# 12V_Buck_For_Auton_LED.net
KiCad netlist of a schematic drawn in Altium Designer
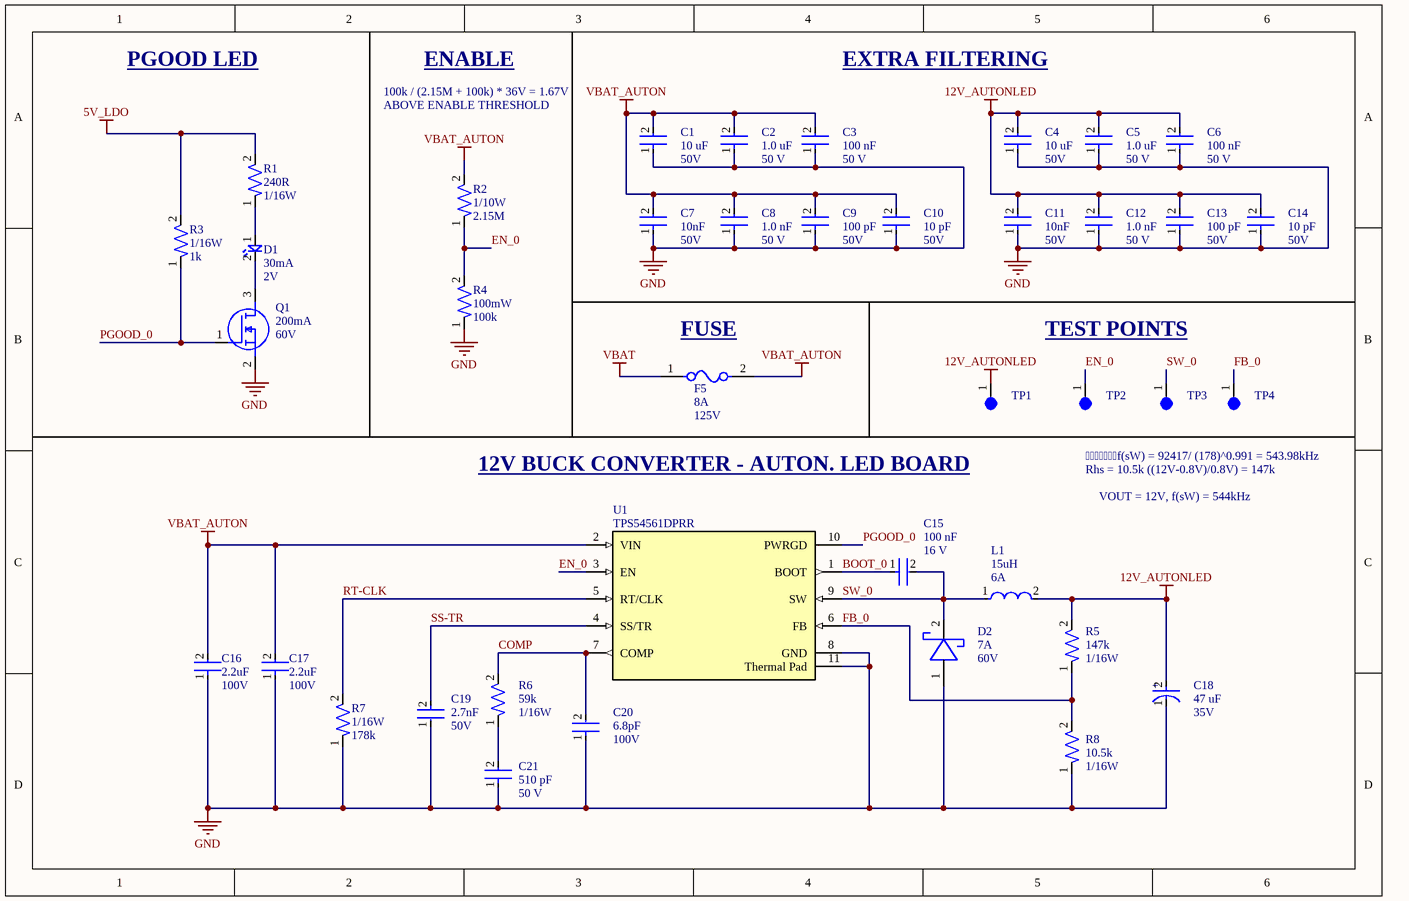
[diagram p0: 12V_Buck_For_Auton_LED.SchDoc]

(export (version "E")
  (design (tool "Eeschema 10.0.6"))
  (components
    (comp (ref "C1")
      (value "CL32B106KBJNNNE")
      (footprint "CAP-1210")
      (description "CAP CER 10UF 50V X7R 1210")
      (fields (field (name "VOLTAGE") "50V") (field (name "CAPACITANCE") "10 uF"))
      (libsource (lib "JLC_25") (part "CAP-10U-0002"))
    )
    (comp (ref "C2")
      (value "CC0805KKX7R9BB105")
      (footprint "CAP-0805")
      (description "CAP CER 1UF 50V X7R 0805")
      (fields (field (name "VOLTAGE") "50 V") (field (name "CAPACITANCE") "1.0 uF"))
      (libsource (lib "JLC_25") (part "CAP-1U-0001"))
    )
    (comp (ref "C3")
      (value "CC0805KRX7R9BB104")
      (footprint "CAP-0805")
      (description "CAP CER 0.1UF 50V X7R 0805")
      (fields (field (name "VOLTAGE RATING") "50 V") (field (name "CAPACITANCE") "100 nF"))
      (libsource (lib "JLC_25") (part "CAP-0.1U-0002"))
    )
    (comp (ref "C4")
      (value "CL32B106KBJNNNE")
      (footprint "CAP-1210")
      (description "CAP CER 10UF 50V X7R 1210")
      (fields (field (name "VOLTAGE") "50V") (field (name "CAPACITANCE") "10 uF"))
      (libsource (lib "JLC_25") (part "CAP-10U-0002"))
    )
    (comp (ref "C5")
      (value "CC0805KKX7R9BB105")
      (footprint "CAP-0805")
      (description "CAP CER 1UF 50V X7R 0805")
      (fields (field (name "VOLTAGE") "50 V") (field (name "CAPACITANCE") "1.0 uF"))
      (libsource (lib "JLC_25") (part "CAP-1U-0001"))
    )
    (comp (ref "C6")
      (value "CC0805KRX7R9BB104")
      (footprint "CAP-0805")
      (description "CAP CER 0.1UF 50V X7R 0805")
      (fields (field (name "VOLTAGE RATING") "50 V") (field (name "CAPACITANCE") "100 nF"))
      (libsource (lib "JLC_25") (part "CAP-0.1U-0002"))
    )
    (comp (ref "C7")
      (value "GRM2195C1H103JA01D")
      (footprint "CAP-0805")
      (description "CAP CER 10000PF 50V C0G/NP0 0805")
      (fields (field (name "VOLTAGE") "50V") (field (name "CAPACITANCE") "10nF"))
      (libsource (lib "JLC_25") (part "CAP-10N-0001"))
    )
    (comp (ref "C8")
      (value "CC0402KRX7R9BB102")
      (footprint "CAP-0402")
      (description "CAP CER 1000PF 50V X7R 0402")
      (fields (field (name "VOLTAGE") "50 V") (field (name "CAPACITANCE") "1.0 nF"))
      (libsource (lib "JLC_25") (part "CAP-1N-0001"))
    )
    (comp (ref "C9")
      (value "CC0402JRNPO9BN101")
      (footprint "CAP-0402")
      (description "CAP CER 100PF 50V C0G/NPO 0402")
      (fields (field (name "CAPACITANCE") "100 pF") (field (name "VOLTAGE") "50V"))
      (libsource (lib "JLC_25") (part "CAP-100P-0001"))
    )
    (comp (ref "C10")
      (value "CC0402JRNPO9BN100")
      (footprint "CAP-0402")
      (description "CAP CER 10PF 50V C0G/NPO 0402")
      (fields (field (name "CAPACITANCE") "10 pF") (field (name "VOLTAGE") "50V"))
      (libsource (lib "JLC_25") (part "CAP-10P-0001"))
    )
    (comp (ref "C11")
      (value "GRM2195C1H103JA01D")
      (footprint "CAP-0805")
      (description "CAP CER 10000PF 50V C0G/NP0 0805")
      (fields (field (name "VOLTAGE") "50V") (field (name "CAPACITANCE") "10nF"))
      (libsource (lib "JLC_25") (part "CAP-10N-0001"))
    )
    (comp (ref "C12")
      (value "CC0402KRX7R9BB102")
      (footprint "CAP-0402")
      (description "CAP CER 1000PF 50V X7R 0402")
      (fields (field (name "VOLTAGE") "50 V") (field (name "CAPACITANCE") "1.0 nF"))
      (libsource (lib "JLC_25") (part "CAP-1N-0001"))
    )
    (comp (ref "C13")
      (value "CC0402JRNPO9BN101")
      (footprint "CAP-0402")
      (description "CAP CER 100PF 50V C0G/NPO 0402")
      (fields (field (name "CAPACITANCE") "100 pF") (field (name "VOLTAGE") "50V"))
      (libsource (lib "JLC_25") (part "CAP-100P-0001"))
    )
    (comp (ref "C14")
      (value "CC0402JRNPO9BN100")
      (footprint "CAP-0402")
      (description "CAP CER 10PF 50V C0G/NPO 0402")
      (fields (field (name "CAPACITANCE") "10 pF") (field (name "VOLTAGE") "50V"))
      (libsource (lib "JLC_25") (part "CAP-10P-0001"))
    )
    (comp (ref "C15")
      (value "CC0402KRX7R7BB104")
      (footprint "CAP-0402")
      (description "CAP CER 0.1UF 16V X7R 0402")
      (fields (field (name "VOLTAGE RATING") "16 V") (field (name "CAPACITANCE") "100 nF"))
      (libsource (lib "JLC_25") (part "CAP-0.1U-0001"))
    )
    (comp (ref "C16")
      (value "CC1206KKX7R0BB225")
      (footprint "CAP-1206")
      (description "CAP CER 2.2UF 100V X7R 1206")
      (fields (field (name "CAPACITANCE") "2.2uF") (field (name "VOLTAGE") "100V"))
      (libsource (lib "JLC_25") (part "CAP-2.2U-0001"))
    )
    (comp (ref "C17")
      (value "CC1206KKX7R0BB225")
      (footprint "CAP-1206")
      (description "CAP CER 2.2UF 100V X7R 1206")
      (fields (field (name "CAPACITANCE") "2.2uF") (field (name "VOLTAGE") "100V"))
      (libsource (lib "JLC_25") (part "CAP-2.2U-0001"))
    )
    (comp (ref "C18")
      (value "EEH-ZC1V470P")
      (footprint "CAP_EEHZC1V470P")
      (description "47 µF 35 V Aluminum - Polymer Capacitors Radial, Can - SMD 60mOhm 4000 Hrs @ 125°C")
      (fields (field (name "VOLTAGE") "35V") (field (name "CAPACITANCE") "47 uF"))
      (libsource (lib "JLC_25") (part "CAP-47U-0003"))
    )
    (comp (ref "C19")
      (value "GRM2165C1H272JA01D")
      (footprint "CAP-0805")
      (description "CAP CER 2700PF 50V C0G/NP0 0805")
      (fields (field (name "VOLTAGE") "50V") (field (name "CAPACITANCE") "2.7nF"))
      (libsource (lib "JLC_25") (part "CAP-2.7N-0001"))
    )
    (comp (ref "C20")
      (value "CC0603CRNPO0BN6R8")
      (footprint "CAP-0603")
      (description "CAP CER 6.8PF 100V C0G/NPO 0603")
      (fields (field (name "VOLTAGE") "100V") (field (name "CAPACITANCE") "6.8pF"))
      (libsource (lib "JLC_25") (part "CAP-6.8P-0001"))
    )
    (comp (ref "C21")
      (value "0402N511J500CT")
      (footprint "CAP-0402")
      (description "CAP CER 510PF 50V C0G/NP0 0402")
      (fields (field (name "VOLTAGE") "50 V") (field (name "CAPACITANCE") "510 pF"))
      (libsource (lib "JLC_25") (part "CAP-510P-0001"))
    )
    (comp (ref "D1")
      (value "BL-HKC36G-AV-TRB")
      (footprint "LED-0603")
      (description "LED YELLOW CLEAR 0603 SMD")
      (fields (field (name "FORWARD CURRENT") "30mA") (field (name "FORWARD VOLTAGE") "2V"))
      (libsource (lib "JLC_25") (part "LED-0001"))
    )
    (comp (ref "D2")
      (value "PDS760-13")
      (footprint "DO-POWERDI5")
      (description "DIODE SCHOTTKY 60V 7A POWERDI5")
      (fields (field (name "FORWARD CURRENT") "7A") (field (name "REVERSE VOLTAGE (DC)") "60V"))
      (libsource (lib "JLC_25") (part "DIO-SCHOTTKY-0001"))
    )
    (comp (ref "F5")
      (value "01550900M")
      (footprint "FUSE-0001")
      (description "FUSE BLOK CARTRIDGE 125V 10A SMD")
      (fields (field (name "FUSE CURRENT") "8A") (field (name "VOLTAGE RATING") "125V"))
      (libsource (lib "JLC_25") (part "FUSE-0001"))
    )
    (comp (ref "L1")
      (value "CSAD1010-150M")
      (footprint "IND-15U-0002")
      (description "SMD MOLDING POWER CHOKE")
      (fields (field (name "INDUCTANCE") "15uH") (field (name "CURRENT RATING") "6A"))
      (libsource (lib "JLC_25") (part "IND-15U-0002-NoJLC"))
    )
    (comp (ref "Q1")
      (value "T2N7002AK,LM")
      (footprint "IC-SOT23-3")
      (description "MOSFET N-CH 60V 200MA SOT23")
      (fields (field (name "CONTINUOUS CURRENT") "200mA") (field (name "VOLTAGE") "60V"))
      (libsource (lib "JLC_25") (part "NMOS-200MA-0001"))
    )
    (comp (ref "R1")
      (value "RC0402FR-07240RL")
      (footprint "RES-0402")
      (description "240R 0.063W 1% 0402 (1005 Metric)  SMD")
      (fields
        (field (name "TOLERANCE") "1%")
        (field (name "RESISTANCE") "240R")
        (field (name "POWER") "1/16W")
      )
      (libsource (lib "JLC_25") (part "RES-240-0001"))
    )
    (comp (ref "R2")
      (value "RC0603FR-072M15L")
      (footprint "RES-0603")
      (description "RES SMD 2.15M OHM 1% 1/10W 0603")
      (fields
        (field (name "TOLERANCE") "1%")
        (field (name "POWER") "1/10W")
        (field (name "RESISTANCE") "2.15M")
      )
      (libsource (lib "JLC_25") (part "RES-2.15M-0001"))
    )
    (comp (ref "R3")
      (value "RC0402FR-071KL")
      (footprint "RES-0402")
      (description "RES 1K OHM 1% 1/16W 0402")
      (fields (field (name "TOLERANCE") "1%") (field (name "POWER") "1/16W") (field (name "RESISTANCE") "1k"))
      (libsource (lib "JLC_25") (part "RES-1k-0001"))
    )
    (comp (ref "R4")
      (value "RC0603FR-07100KL")
      (footprint "RES-0603")
      (description "RES SMD 100K OHM 1% 1/10W 0603")
      (fields
        (field (name "TOLERANCE") "1%")
        (field (name "POWER") "100mW")
        (field (name "RESISTANCE") "100k")
      )
      (libsource (lib "JLC_25") (part "RES-100k-0001"))
    )
    (comp (ref "R5")
      (value "RC0402FR-07147KL")
      (footprint "RES-0402")
      (description "RES 147K OHM 1% 1/16W 0402")
      (fields
        (field (name "TOLERANCE") "1%")
        (field (name "POWER") "1/16W")
        (field (name "RESISTANCE") "147k")
      )
      (libsource (lib "JLC_25") (part "RES-147k-0001"))
    )
    (comp (ref "R6")
      (value "RC0402FR-0759KL")
      (footprint "RES-0402")
      (description "RES 59K OHM 1% 1/16W 0402")
      (fields
        (field (name "TOLERANCE") "1%")
        (field (name "POWER") "1/16W")
        (field (name "RESISTANCE") "59k")
      )
      (libsource (lib "JLC_25") (part "RES-59k-0001"))
    )
    (comp (ref "R7")
      (value "RTT021783FTH")
      (footprint "RES-0402")
      (description "62.5mW Thick Film Resistors 50V ±100ppm/℃ ±1% 178kΩ 0402 Chip Resistor - Surface Mount ROHS")
      (fields
        (field (name "TOLERANCE") "1%")
        (field (name "POWER") "1/16W")
        (field (name "RESISTANCE") "178k")
      )
      (libsource (lib "JLC_25") (part "RES-178k-0001_1"))
    )
    (comp (ref "R8")
      (value "RC0402FR-0710K5L")
      (footprint "RES-0402")
      (description "RES 10.5K OHM 1% 1/16W 0402")
      (fields
        (field (name "TOLERANCE") "1%")
        (field (name "POWER") "1/16W")
        (field (name "RESISTANCE") "10.5k")
      )
      (libsource (lib "JLC_25") (part "RES-10.5k-0001"))
    )
    (comp (ref "TP1")
      (value "5003")
      (footprint "TEST-POINT-0001")
      (description "Oranange PC Test Point, Miniature Phoisphor Bronze Silver Plating Through Hole Mounting Type")
      (libsource (lib "*") (part "TEST-POINT-0001"))
    )
    (comp (ref "TP2")
      (value "5003")
      (footprint "TEST-POINT-0001")
      (description "Oranange PC Test Point, Miniature Phoisphor Bronze Silver Plating Through Hole Mounting Type")
      (libsource (lib "*") (part "TEST-POINT-0001"))
    )
    (comp (ref "TP3")
      (value "5003")
      (footprint "TEST-POINT-0001")
      (description "Oranange PC Test Point, Miniature Phoisphor Bronze Silver Plating Through Hole Mounting Type")
      (libsource (lib "*") (part "TEST-POINT-0001"))
    )
    (comp (ref "TP4")
      (value "5003")
      (footprint "TEST-POINT-0001")
      (description "Oranange PC Test Point, Miniature Phoisphor Bronze Silver Plating Through Hole Mounting Type")
      (libsource (lib "*") (part "TEST-POINT-0001"))
    )
    (comp (ref "U1")
      (value "TPS54561DPRR")
      (footprint "IC-10WSON")
      (description "IC REG BUCK ADJ 5A 10WSON")
      (libsource (lib "JLC_25") (part "IC-BUCK-0001"))
    )
  )
  (nets
    (net (code "1") (name "/BOOT_0") (class "Default")
      (node (ref "C15") (pin "1") (pinfunction "1_1") (pintype "passive"))
      (node (ref "U1") (pin "1") (pinfunction "BOOT_1") (pintype "output"))
    )
    (net (code "2") (name "/COMP") (class "Default")
      (node (ref "C20") (pin "2") (pinfunction "2_2") (pintype "passive"))
      (node (ref "R6") (pin "2") (pinfunction "2_2") (pintype "passive"))
      (node (ref "U1") (pin "7") (pinfunction "COMP_7") (pintype "output"))
    )
    (net (code "3") (name "/EN_0") (class "Default")
      (node (ref "R2") (pin "1") (pinfunction "1_1") (pintype "passive"))
      (node (ref "R4") (pin "2") (pinfunction "2_2") (pintype "passive"))
      (node (ref "TP2") (pin "1") (pinfunction "0_1") (pintype "passive"))
      (node (ref "U1") (pin "3") (pinfunction "EN_3") (pintype "input"))
    )
    (net (code "4") (name "/FB_0") (class "Default")
      (node (ref "R5") (pin "1") (pinfunction "1_1") (pintype "passive"))
      (node (ref "R8") (pin "2") (pinfunction "2_2") (pintype "passive"))
      (node (ref "TP4") (pin "1") (pinfunction "0_1") (pintype "passive"))
      (node (ref "U1") (pin "6") (pinfunction "FB_6") (pintype "input"))
    )
    (net (code "5") (name "/PGOOD_0") (class "Default")
      (node (ref "Q1") (pin "1") (pinfunction "G_1") (pintype "passive"))
      (node (ref "R3") (pin "1") (pinfunction "1_1") (pintype "passive"))
      (node (ref "U1") (pin "10") (pinfunction "PWRGD_10") (pintype "open_collector"))
    )
    (net (code "6") (name "/RT-CLK") (class "Default")
      (node (ref "R7") (pin "2") (pinfunction "2_2") (pintype "passive"))
      (node (ref "U1") (pin "5") (pinfunction "RT/CLK_5") (pintype "input"))
    )
    (net (code "7") (name "/SS-TR") (class "Default")
      (node (ref "C19") (pin "2") (pinfunction "2_2") (pintype "passive"))
      (node (ref "U1") (pin "4") (pinfunction "SS/TR_4") (pintype "input"))
    )
    (net (code "8") (name "/SW_0") (class "Default")
      (node (ref "C15") (pin "2") (pinfunction "2_2") (pintype "passive"))
      (node (ref "D2") (pin "2") (pinfunction "ANODE_2") (pintype "passive"))
      (node (ref "L1") (pin "1") (pinfunction "1_1") (pintype "passive"))
      (node (ref "TP3") (pin "1") (pinfunction "0_1") (pintype "passive"))
      (node (ref "U1") (pin "9") (pinfunction "SW_9") (pintype "input"))
    )
    (net (code "9") (name "5V_LDO") (class "Default")
      (node (ref "R1") (pin "2") (pinfunction "2_2") (pintype "passive"))
      (node (ref "R3") (pin "2") (pinfunction "2_2") (pintype "passive"))
    )
    (net (code "10") (name "12V_AUTONLED") (class "Default")
      (node (ref "C11") (pin "2") (pinfunction "2_2") (pintype "passive"))
      (node (ref "C12") (pin "2") (pinfunction "2_2") (pintype "passive"))
      (node (ref "C13") (pin "2") (pinfunction "2_2") (pintype "passive"))
      (node (ref "C14") (pin "2") (pinfunction "2_2") (pintype "passive"))
      (node (ref "C18") (pin "2") (pinfunction "A_2") (pintype "passive"))
      (node (ref "C4") (pin "2") (pinfunction "2_2") (pintype "passive"))
      (node (ref "C5") (pin "2") (pinfunction "2_2") (pintype "passive"))
      (node (ref "C6") (pin "2") (pinfunction "2_2") (pintype "passive"))
      (node (ref "L1") (pin "2") (pinfunction "2_2") (pintype "passive"))
      (node (ref "R5") (pin "2") (pinfunction "2_2") (pintype "passive"))
      (node (ref "TP1") (pin "1") (pinfunction "0_1") (pintype "passive"))
    )
    (net (code "11") (name "GND") (class "Default")
      (node (ref "C1") (pin "1") (pinfunction "1_1") (pintype "passive"))
      (node (ref "C10") (pin "1") (pinfunction "1_1") (pintype "passive"))
      (node (ref "C11") (pin "1") (pinfunction "1_1") (pintype "passive"))
      (node (ref "C12") (pin "1") (pinfunction "1_1") (pintype "passive"))
      (node (ref "C13") (pin "1") (pinfunction "1_1") (pintype "passive"))
      (node (ref "C14") (pin "1") (pinfunction "1_1") (pintype "passive"))
      (node (ref "C16") (pin "1") (pinfunction "1_1") (pintype "passive"))
      (node (ref "C17") (pin "1") (pinfunction "1_1") (pintype "passive"))
      (node (ref "C18") (pin "1") (pinfunction "C_1") (pintype "passive"))
      (node (ref "C19") (pin "1") (pinfunction "1_1") (pintype "passive"))
      (node (ref "C2") (pin "1") (pinfunction "1_1") (pintype "passive"))
      (node (ref "C20") (pin "1") (pinfunction "1_1") (pintype "passive"))
      (node (ref "C21") (pin "1") (pinfunction "1_1") (pintype "passive"))
      (node (ref "C3") (pin "1") (pinfunction "1_1") (pintype "passive"))
      (node (ref "C4") (pin "1") (pinfunction "1_1") (pintype "passive"))
      (node (ref "C5") (pin "1") (pinfunction "1_1") (pintype "passive"))
      (node (ref "C6") (pin "1") (pinfunction "1_1") (pintype "passive"))
      (node (ref "C7") (pin "1") (pinfunction "1_1") (pintype "passive"))
      (node (ref "C8") (pin "1") (pinfunction "1_1") (pintype "passive"))
      (node (ref "C9") (pin "1") (pinfunction "1_1") (pintype "passive"))
      (node (ref "D2") (pin "1") (pinfunction "CATHODE_1") (pintype "passive"))
      (node (ref "Q1") (pin "2") (pinfunction "S_2") (pintype "passive"))
      (node (ref "R4") (pin "1") (pinfunction "1_1") (pintype "passive"))
      (node (ref "R7") (pin "1") (pinfunction "1_1") (pintype "passive"))
      (node (ref "R8") (pin "1") (pinfunction "1_1") (pintype "passive"))
      (node (ref "U1") (pin "11") (pinfunction "Thermal_Pad_11") (pintype "power_in"))
      (node (ref "U1") (pin "8") (pinfunction "GND_8") (pintype "power_in"))
    )
    (net (code "12") (name "Net-(C21-Pad2)") (class "Default")
      (node (ref "C21") (pin "2") (pinfunction "2_2") (pintype "passive"))
      (node (ref "R6") (pin "1") (pinfunction "1_1") (pintype "passive"))
    )
    (net (code "13") (name "Net-(D1-Pad1)") (class "Default")
      (node (ref "D1") (pin "1") (pinfunction "1_1") (pintype "passive"))
      (node (ref "R1") (pin "1") (pinfunction "1_1") (pintype "passive"))
    )
    (net (code "14") (name "Net-(Q1-D)") (class "Default")
      (node (ref "D1") (pin "2") (pinfunction "2_2") (pintype "passive"))
      (node (ref "Q1") (pin "3") (pinfunction "D_3") (pintype "passive"))
    )
    (net (code "15") (name "VBAT") (class "Default")
      (node (ref "F5") (pin "1") (pinfunction "1_1") (pintype "passive"))
    )
    (net (code "16") (name "VBAT_AUTON") (class "Default")
      (node (ref "C1") (pin "2") (pinfunction "2_2") (pintype "passive"))
      (node (ref "C10") (pin "2") (pinfunction "2_2") (pintype "passive"))
      (node (ref "C16") (pin "2") (pinfunction "2_2") (pintype "passive"))
      (node (ref "C17") (pin "2") (pinfunction "2_2") (pintype "passive"))
      (node (ref "C2") (pin "2") (pinfunction "2_2") (pintype "passive"))
      (node (ref "C3") (pin "2") (pinfunction "2_2") (pintype "passive"))
      (node (ref "C7") (pin "2") (pinfunction "2_2") (pintype "passive"))
      (node (ref "C8") (pin "2") (pinfunction "2_2") (pintype "passive"))
      (node (ref "C9") (pin "2") (pinfunction "2_2") (pintype "passive"))
      (node (ref "F5") (pin "2") (pinfunction "2_2") (pintype "passive"))
      (node (ref "R2") (pin "2") (pinfunction "2_2") (pintype "passive"))
      (node (ref "U1") (pin "2") (pinfunction "VIN_2") (pintype "input"))
    )
  )
)
